# WGPIB.net
KiCad netlist of a schematic drawn in Altium Designer
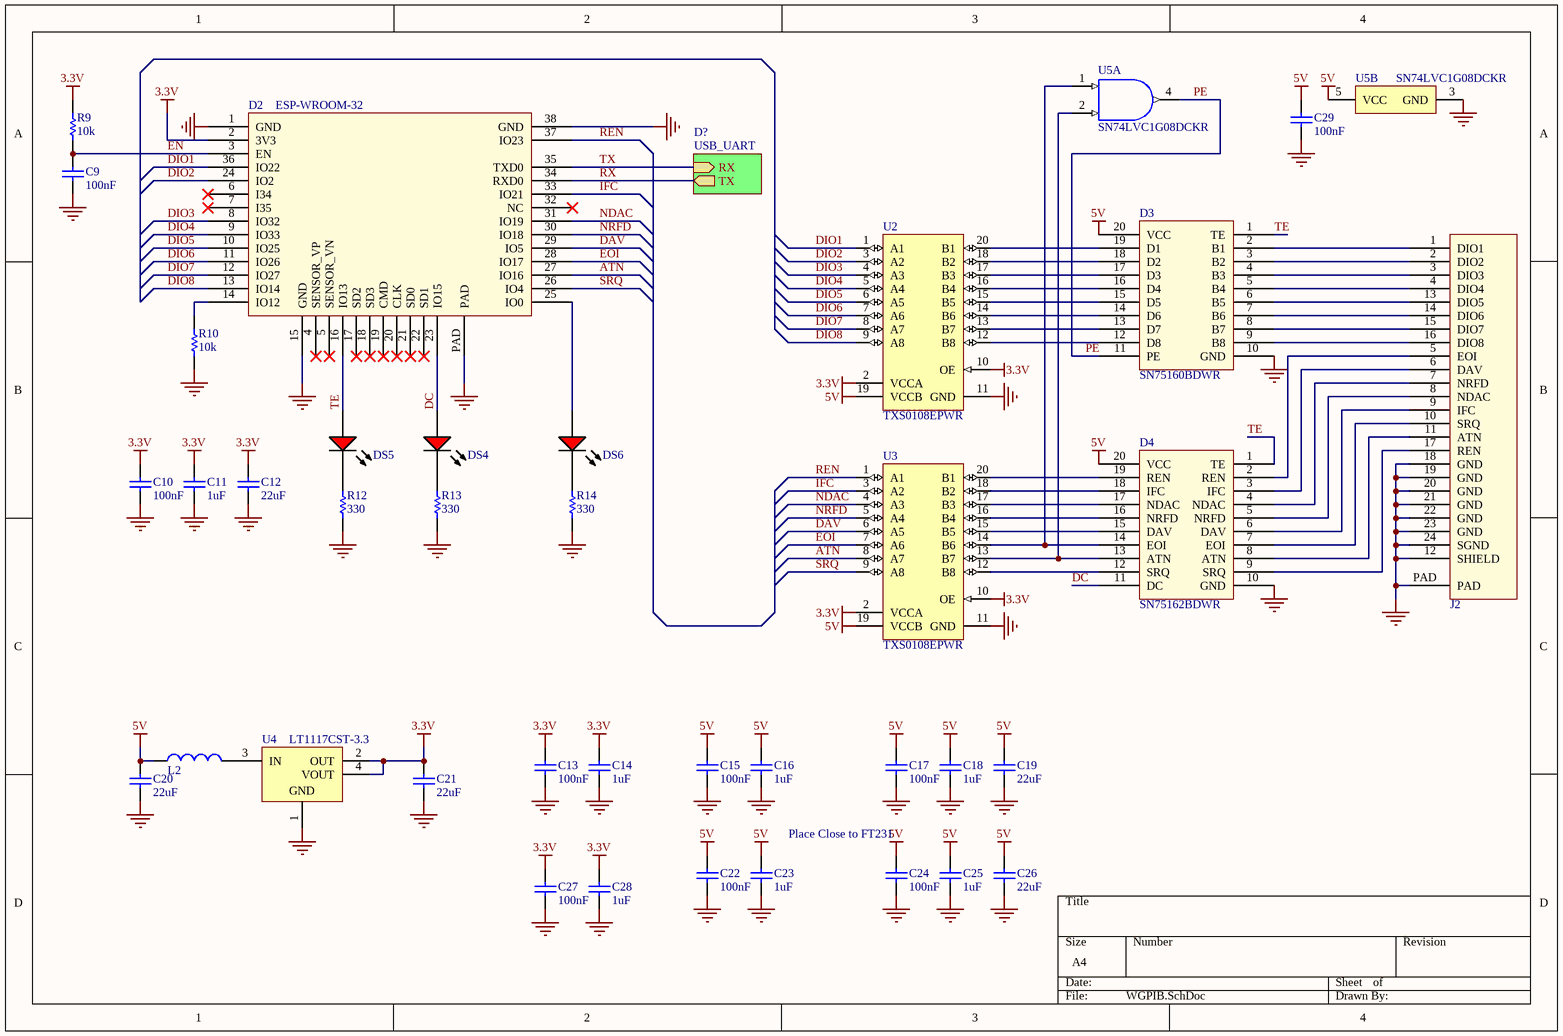
[diagram p0: WGPIB.SchDoc]

(export (version "E")
  (design (tool "Eeschema 10.0.6"))
  (components
    (comp (ref "C9")
      (value "100nF")
      (footprint "CAPC0805(2012)145_N")
      (fields (field (name "TOLERANCE") "Â±20%"))
      (libsource (lib "Altium Content Vault") (part "CAP"))
    )
    (comp (ref "C10")
      (value "100nF")
      (footprint "CAPC0805(2012)145_N")
      (fields (field (name "TOLERANCE") "Â±20%"))
      (libsource (lib "Altium Content Vault") (part "CAP"))
    )
    (comp (ref "C11")
      (value "1uF")
      (footprint "CAPC0805(2012)145_N")
      (fields (field (name "TOLERANCE") "Â±20%"))
      (libsource (lib "Altium Content Vault") (part "CAP"))
    )
    (comp (ref "C12")
      (value "22uF")
      (footprint "CAPC1206(3216)190_M")
      (fields (field (name "TOLERANCE") "Â±20%"))
      (libsource (lib "Altium Content Vault") (part "CAP"))
    )
    (comp (ref "C13")
      (value "100nF")
      (footprint "CAPC0805(2012)145_N")
      (fields (field (name "TOLERANCE") "Â±20%"))
      (libsource (lib "Altium Content Vault") (part "CAP"))
    )
    (comp (ref "C14")
      (value "1uF")
      (footprint "CAPC0805(2012)145_N")
      (fields (field (name "TOLERANCE") "Â±20%"))
      (libsource (lib "Altium Content Vault") (part "CAP"))
    )
    (comp (ref "C15")
      (value "100nF")
      (footprint "CAPC0805(2012)145_N")
      (fields (field (name "TOLERANCE") "Â±20%"))
      (libsource (lib "Altium Content Vault") (part "CAP"))
    )
    (comp (ref "C16")
      (value "1uF")
      (footprint "CAPC0805(2012)145_N")
      (fields (field (name "TOLERANCE") "Â±20%"))
      (libsource (lib "Altium Content Vault") (part "CAP"))
    )
    (comp (ref "C17")
      (value "100nF")
      (footprint "CAPC0805(2012)145_N")
      (fields (field (name "TOLERANCE") "Â±20%"))
      (libsource (lib "Altium Content Vault") (part "CAP"))
    )
    (comp (ref "C18")
      (value "1uF")
      (footprint "CAPC0805(2012)145_N")
      (fields (field (name "TOLERANCE") "Â±20%"))
      (libsource (lib "Altium Content Vault") (part "CAP"))
    )
    (comp (ref "C19")
      (value "22uF")
      (footprint "CAPC1206(3216)190_M")
      (fields (field (name "TOLERANCE") "Â±20%"))
      (libsource (lib "Altium Content Vault") (part "CAP"))
    )
    (comp (ref "C20")
      (value "22uF")
      (footprint "CAPC1206(3216)190_M")
      (fields (field (name "TOLERANCE") "Â±20%"))
      (libsource (lib "Altium Content Vault") (part "CAP"))
    )
    (comp (ref "C21")
      (value "22uF")
      (footprint "CAPC1206(3216)190_M")
      (fields (field (name "TOLERANCE") "Â±20%"))
      (libsource (lib "Altium Content Vault") (part "CAP"))
    )
    (comp (ref "C22")
      (value "100nF")
      (footprint "CAPC0805(2012)145_N")
      (fields (field (name "TOLERANCE") "Â±20%"))
      (libsource (lib "Altium Content Vault") (part "CAP"))
    )
    (comp (ref "C23")
      (value "1uF")
      (footprint "CAPC0805(2012)145_N")
      (fields (field (name "TOLERANCE") "Â±20%"))
      (libsource (lib "Altium Content Vault") (part "CAP"))
    )
    (comp (ref "C24")
      (value "100nF")
      (footprint "CAPC0805(2012)145_N")
      (fields (field (name "TOLERANCE") "Â±20%"))
      (libsource (lib "Altium Content Vault") (part "CAP"))
    )
    (comp (ref "C25")
      (value "1uF")
      (footprint "CAPC0805(2012)145_N")
      (fields (field (name "TOLERANCE") "Â±20%"))
      (libsource (lib "Altium Content Vault") (part "CAP"))
    )
    (comp (ref "C26")
      (value "22uF")
      (footprint "CAPC1206(3216)190_M")
      (fields (field (name "TOLERANCE") "Â±20%"))
      (libsource (lib "Altium Content Vault") (part "CAP"))
    )
    (comp (ref "C27")
      (value "100nF")
      (footprint "CAPC0805(2012)145_N")
      (fields (field (name "TOLERANCE") "Â±20%"))
      (libsource (lib "Altium Content Vault") (part "CAP"))
    )
    (comp (ref "C28")
      (value "1uF")
      (footprint "CAPC0805(2012)145_N")
      (fields (field (name "TOLERANCE") "Â±20%"))
      (libsource (lib "Altium Content Vault") (part "CAP"))
    )
    (comp (ref "C29")
      (value "100nF")
      (footprint "CAPC0805(2012)145_N")
      (fields (field (name "TOLERANCE") "Â±20%"))
      (libsource (lib "Altium Content Vault") (part "CAP"))
    )
    (comp (ref "D2")
      (value "ESP-WROOM-32")
      (footprint "ESP-WROOM-32")
      (description "ESP32 Module")
      (libsource (lib "DEV_Modules") (part "ESP-WROOM-32"))
    )
    (comp (ref "D3")
      (value "SN75160BDWR")
      (footprint "SOIC-20")
      (libsource (lib "LineDrivers") (part "SN75160BDWR"))
    )
    (comp (ref "D4")
      (value "SN75162BDWR")
      (footprint "SOIC-20")
      (libsource (lib "LineDrivers") (part "SN75161BDWR"))
    )
    (comp (ref "DS4")
      (value "TLMS1100-GS08")
      (footprint "VISH-TLMX1100_V")
      (description "LED, RED, 2.1 V, -40 to 100 degC, 2-Pin SMD (0603), RoHS, Tape and Reel")
      (fields (field (name "TOLERANCE") "5%"))
      (libsource (lib "Altium Content Vault") (part "LED-RED-AK-2"))
    )
    (comp (ref "DS5")
      (value "TLMS1100-GS08")
      (footprint "VISH-TLMX1100_V")
      (description "LED, RED, 2.1 V, -40 to 100 degC, 2-Pin SMD (0603), RoHS, Tape and Reel")
      (fields (field (name "TOLERANCE") "5%"))
      (libsource (lib "Altium Content Vault") (part "LED-RED-AK-2"))
    )
    (comp (ref "DS6")
      (value "TLMS1100-GS08")
      (footprint "VISH-TLMX1100_V")
      (description "LED, RED, 2.1 V, -40 to 100 degC, 2-Pin SMD (0603), RoHS, Tape and Reel")
      (fields (field (name "TOLERANCE") "5%"))
      (libsource (lib "Altium Content Vault") (part "LED-RED-AK-2"))
    )
    (comp (ref "J2")
      (value "GPIB")
      (footprint "GPIB THT")
      (description "112-024-113R001")
      (libsource (lib "DSUB_Connector") (part "GPIB"))
    )
    (comp (ref "L2")
      (value "FBMJ2125HM210NT")
      (footprint "INDC2013X105X50LL20T30")
      (description "Chip Inductor, 21 Ohm, +/- 30%, 6 A, -40 to 125 degC, 0805 (2012 Metric), RoHS, Tape and Reel")
      (fields (field (name "TOLERANCE") "30%"))
      (libsource (lib "Altium Content Vault") (part "IND-2"))
    )
    (comp (ref "R9")
      (value "10k")
      (footprint "RESC0805(2012)_M")
      (fields (field (name "POWER") "0.125 W") (field (name "TOLERANCE") "5 %"))
      (libsource (lib "Altium Content Vault") (part "RES"))
    )
    (comp (ref "R10")
      (value "10k")
      (footprint "RESC0805(2012)_M")
      (fields (field (name "POWER") "0.125 W") (field (name "TOLERANCE") "5 %"))
      (libsource (lib "Altium Content Vault") (part "RES"))
    )
    (comp (ref "R12")
      (value "330")
      (footprint "RESC0805(2012)_M")
      (fields (field (name "POWER") "0.125 W") (field (name "TOLERANCE") "5 %"))
      (libsource (lib "Altium Content Vault") (part "RES"))
    )
    (comp (ref "R13")
      (value "330")
      (footprint "RESC0805(2012)_M")
      (fields (field (name "POWER") "0.125 W") (field (name "TOLERANCE") "5 %"))
      (libsource (lib "Altium Content Vault") (part "RES"))
    )
    (comp (ref "R14")
      (value "330")
      (footprint "RESC0805(2012)_M")
      (fields (field (name "POWER") "0.125 W") (field (name "TOLERANCE") "5 %"))
      (libsource (lib "Altium Content Vault") (part "RES"))
    )
    (comp (ref "U2")
      (value "TXS0108EPWR")
      (footprint "PW0020A_M")
      (fields (field (name "MANUFACTURER") "Texas Instruments"))
      (libsource (lib "Altium Content Vault") (part "TI-TXS0108EPWR-SOP-20"))
    )
    (comp (ref "U3")
      (value "TXS0108EPWR")
      (footprint "PW0020A_M")
      (fields (field (name "MANUFACTURER") "Texas Instruments"))
      (libsource (lib "Altium Content Vault") (part "TI-TXS0108EPWR-SOP-20"))
    )
    (comp (ref "U4")
      (value "LT1117CST-3.3")
      (footprint "LT-ST-3-SOT-223_M")
      (fields (field (name "MANUFACTURER") "Linear Technology"))
      (libsource (lib "Altium Content Vault") (part "LT-LT1117-3_B"))
    )
    (comp (ref "U5")
      (value "SN74LVC1G08DCKR")
      (footprint "DCK0005A_M")
      (description "Single 2-Input Positive-AND Gate, DCK0005A, LARGE T&R")
      (fields
        (field (name "GENERIC PART NUMBER") "SN74LVC1G08")
        (field (name "MANUFACTURER") "Texas Instruments")
      )
      (libsource (lib "Altium Content Vault") (part "TI-SN74XXX1X08-5"))
    )
  )
  (nets
    (net (code "1") (name "/ATN") (class "Default")
      (node (ref "D2") (pin "27") (pinfunction "IO16_27") (pintype "passive"))
      (node (ref "U3") (pin "8") (pinfunction "A7_8") (pintype "bidirectional"))
    )
    (net (code "2") (name "/DAV") (class "Default")
      (node (ref "D2") (pin "29") (pinfunction "IO5_29") (pintype "passive"))
      (node (ref "U3") (pin "6") (pinfunction "A5_6") (pintype "bidirectional"))
    )
    (net (code "3") (name "/DC") (class "Default")
      (node (ref "D2") (pin "23") (pinfunction "IO15_23") (pintype "passive"))
      (node (ref "D4") (pin "11") (pinfunction "DC_11") (pintype "passive"))
      (node (ref "DS4") (pin "1") (pinfunction "A_1") (pintype "passive"))
    )
    (net (code "4") (name "/DIO1") (class "Default")
      (node (ref "D2") (pin "36") (pinfunction "IO22_36") (pintype "passive"))
      (node (ref "U2") (pin "1") (pinfunction "A1_1") (pintype "bidirectional"))
    )
    (net (code "5") (name "/DIO2") (class "Default")
      (node (ref "D2") (pin "24") (pinfunction "IO2_24") (pintype "passive"))
      (node (ref "U2") (pin "3") (pinfunction "A2_3") (pintype "bidirectional"))
    )
    (net (code "6") (name "/DIO3") (class "Default")
      (node (ref "D2") (pin "8") (pinfunction "IO32_8") (pintype "passive"))
      (node (ref "U2") (pin "4") (pinfunction "A3_4") (pintype "bidirectional"))
    )
    (net (code "7") (name "/DIO4") (class "Default")
      (node (ref "D2") (pin "9") (pinfunction "IO33_9") (pintype "passive"))
      (node (ref "U2") (pin "5") (pinfunction "A4_5") (pintype "bidirectional"))
    )
    (net (code "8") (name "/DIO5") (class "Default")
      (node (ref "D2") (pin "10") (pinfunction "IO25_10") (pintype "passive"))
      (node (ref "U2") (pin "6") (pinfunction "A5_6") (pintype "bidirectional"))
    )
    (net (code "9") (name "/DIO6") (class "Default")
      (node (ref "D2") (pin "11") (pinfunction "IO26_11") (pintype "passive"))
      (node (ref "U2") (pin "7") (pinfunction "A6_7") (pintype "bidirectional"))
    )
    (net (code "10") (name "/DIO7") (class "Default")
      (node (ref "D2") (pin "12") (pinfunction "IO27_12") (pintype "passive"))
      (node (ref "U2") (pin "8") (pinfunction "A7_8") (pintype "bidirectional"))
    )
    (net (code "11") (name "/DIO8") (class "Default")
      (node (ref "D2") (pin "13") (pinfunction "IO14_13") (pintype "passive"))
      (node (ref "U2") (pin "9") (pinfunction "A8_9") (pintype "bidirectional"))
    )
    (net (code "12") (name "/EN") (class "Default")
      (node (ref "C9") (pin "2") (pinfunction "2_2") (pintype "passive"))
      (node (ref "D2") (pin "3") (pinfunction "EN_3") (pintype "passive"))
      (node (ref "R9") (pin "1") (pinfunction "1_1") (pintype "passive"))
    )
    (net (code "13") (name "/EOI") (class "Default")
      (node (ref "D2") (pin "28") (pinfunction "IO17_28") (pintype "passive"))
      (node (ref "U3") (pin "7") (pinfunction "A6_7") (pintype "bidirectional"))
    )
    (net (code "14") (name "/IFC") (class "Default")
      (node (ref "D2") (pin "33") (pinfunction "IO21_33") (pintype "passive"))
      (node (ref "U3") (pin "3") (pinfunction "A2_3") (pintype "bidirectional"))
    )
    (net (code "15") (name "/NDAC") (class "Default")
      (node (ref "D2") (pin "31") (pinfunction "IO19_31") (pintype "passive"))
      (node (ref "U3") (pin "4") (pinfunction "A3_4") (pintype "bidirectional"))
    )
    (net (code "16") (name "/NRFD") (class "Default")
      (node (ref "D2") (pin "30") (pinfunction "IO18_30") (pintype "passive"))
      (node (ref "U3") (pin "5") (pinfunction "A4_5") (pintype "bidirectional"))
    )
    (net (code "17") (name "/PE") (class "Default")
      (node (ref "D3") (pin "11") (pinfunction "PE_11") (pintype "passive"))
      (node (ref "U5") (pin "4") (pinfunction "Y_4") (pintype "output"))
    )
    (net (code "18") (name "/REN") (class "Default")
      (node (ref "D2") (pin "37") (pinfunction "IO23_37") (pintype "passive"))
      (node (ref "U3") (pin "1") (pinfunction "A1_1") (pintype "bidirectional"))
    )
    (net (code "19") (name "/RX") (class "Default")
      (node (ref "D2") (pin "34") (pinfunction "RXD0_34") (pintype "passive"))
    )
    (net (code "20") (name "/SRQ") (class "Default")
      (node (ref "D2") (pin "26") (pinfunction "IO4_26") (pintype "passive"))
      (node (ref "U3") (pin "9") (pinfunction "A8_9") (pintype "bidirectional"))
    )
    (net (code "21") (name "/TE") (class "Default")
      (node (ref "D2") (pin "16") (pinfunction "IO13_16") (pintype "passive"))
      (node (ref "D3") (pin "1") (pinfunction "TE_1") (pintype "passive"))
      (node (ref "D4") (pin "1") (pinfunction "TE_1") (pintype "passive"))
      (node (ref "DS5") (pin "1") (pinfunction "A_1") (pintype "passive"))
    )
    (net (code "22") (name "/TX") (class "Default")
      (node (ref "D2") (pin "35") (pinfunction "TXD0_35") (pintype "passive"))
    )
    (net (code "23") (name "3.3V") (class "Default")
      (node (ref "C10") (pin "2") (pinfunction "2_2") (pintype "passive"))
      (node (ref "C11") (pin "2") (pinfunction "2_2") (pintype "passive"))
      (node (ref "C12") (pin "2") (pinfunction "2_2") (pintype "passive"))
      (node (ref "C13") (pin "2") (pinfunction "2_2") (pintype "passive"))
      (node (ref "C14") (pin "2") (pinfunction "2_2") (pintype "passive"))
      (node (ref "C21") (pin "2") (pinfunction "2_2") (pintype "passive"))
      (node (ref "C27") (pin "2") (pinfunction "2_2") (pintype "passive"))
      (node (ref "C28") (pin "2") (pinfunction "2_2") (pintype "passive"))
      (node (ref "D2") (pin "2") (pinfunction "3V3_2") (pintype "passive"))
      (node (ref "R9") (pin "2") (pinfunction "2_2") (pintype "passive"))
      (node (ref "U2") (pin "10") (pinfunction "OE_10") (pintype "input"))
      (node (ref "U2") (pin "2") (pinfunction "VCCA_2") (pintype "power_in"))
      (node (ref "U3") (pin "10") (pinfunction "OE_10") (pintype "input"))
      (node (ref "U3") (pin "2") (pinfunction "VCCA_2") (pintype "power_in"))
      (node (ref "U4") (pin "2") (pinfunction "OUT_2") (pintype "power_in"))
      (node (ref "U4") (pin "4") (pinfunction "VOUT_4") (pintype "power_in"))
    )
    (net (code "24") (name "5V") (class "Default")
      (node (ref "C15") (pin "2") (pinfunction "2_2") (pintype "passive"))
      (node (ref "C16") (pin "2") (pinfunction "2_2") (pintype "passive"))
      (node (ref "C17") (pin "2") (pinfunction "2_2") (pintype "passive"))
      (node (ref "C18") (pin "2") (pinfunction "2_2") (pintype "passive"))
      (node (ref "C19") (pin "2") (pinfunction "2_2") (pintype "passive"))
      (node (ref "C20") (pin "2") (pinfunction "2_2") (pintype "passive"))
      (node (ref "C22") (pin "2") (pinfunction "2_2") (pintype "passive"))
      (node (ref "C23") (pin "2") (pinfunction "2_2") (pintype "passive"))
      (node (ref "C24") (pin "2") (pinfunction "2_2") (pintype "passive"))
      (node (ref "C25") (pin "2") (pinfunction "2_2") (pintype "passive"))
      (node (ref "C26") (pin "2") (pinfunction "2_2") (pintype "passive"))
      (node (ref "C29") (pin "2") (pinfunction "2_2") (pintype "passive"))
      (node (ref "D3") (pin "20") (pinfunction "VCC_20") (pintype "passive"))
      (node (ref "D4") (pin "20") (pinfunction "VCC_20") (pintype "passive"))
      (node (ref "L2") (pin "1") (pinfunction "1_1") (pintype "passive"))
      (node (ref "U2") (pin "19") (pinfunction "VCCB_19") (pintype "power_in"))
      (node (ref "U3") (pin "19") (pinfunction "VCCB_19") (pintype "power_in"))
      (node (ref "U5") (pin "5") (pinfunction "VCC_5") (pintype "power_in"))
    )
    (net (code "25") (name "GND") (class "Default")
      (node (ref "C10") (pin "1") (pinfunction "1_1") (pintype "passive"))
      (node (ref "C11") (pin "1") (pinfunction "1_1") (pintype "passive"))
      (node (ref "C12") (pin "1") (pinfunction "1_1") (pintype "passive"))
      (node (ref "C13") (pin "1") (pinfunction "1_1") (pintype "passive"))
      (node (ref "C14") (pin "1") (pinfunction "1_1") (pintype "passive"))
      (node (ref "C15") (pin "1") (pinfunction "1_1") (pintype "passive"))
      (node (ref "C16") (pin "1") (pinfunction "1_1") (pintype "passive"))
      (node (ref "C17") (pin "1") (pinfunction "1_1") (pintype "passive"))
      (node (ref "C18") (pin "1") (pinfunction "1_1") (pintype "passive"))
      (node (ref "C19") (pin "1") (pinfunction "1_1") (pintype "passive"))
      (node (ref "C20") (pin "1") (pinfunction "1_1") (pintype "passive"))
      (node (ref "C21") (pin "1") (pinfunction "1_1") (pintype "passive"))
      (node (ref "C22") (pin "1") (pinfunction "1_1") (pintype "passive"))
      (node (ref "C23") (pin "1") (pinfunction "1_1") (pintype "passive"))
      (node (ref "C24") (pin "1") (pinfunction "1_1") (pintype "passive"))
      (node (ref "C25") (pin "1") (pinfunction "1_1") (pintype "passive"))
      (node (ref "C26") (pin "1") (pinfunction "1_1") (pintype "passive"))
      (node (ref "C27") (pin "1") (pinfunction "1_1") (pintype "passive"))
      (node (ref "C28") (pin "1") (pinfunction "1_1") (pintype "passive"))
      (node (ref "C29") (pin "1") (pinfunction "1_1") (pintype "passive"))
      (node (ref "C9") (pin "1") (pinfunction "1_1") (pintype "passive"))
      (node (ref "D2") (pin "1") (pinfunction "GND_1") (pintype "passive"))
      (node (ref "D2") (pin "15") (pinfunction "GND_15") (pintype "passive"))
      (node (ref "D2") (pin "38") (pinfunction "GND_38") (pintype "passive"))
      (node (ref "D2") (pin "PAD") (pinfunction "PAD_PAD") (pintype "passive"))
      (node (ref "D3") (pin "10") (pinfunction "GND_10") (pintype "passive"))
      (node (ref "D4") (pin "10") (pinfunction "GND_10") (pintype "passive"))
      (node (ref "J2") (pin "12") (pinfunction "SHIELD_12") (pintype "passive"))
      (node (ref "J2") (pin "18") (pinfunction "GND_18") (pintype "passive"))
      (node (ref "J2") (pin "19") (pinfunction "GND_19") (pintype "passive"))
      (node (ref "J2") (pin "20") (pinfunction "GND_20") (pintype "passive"))
      (node (ref "J2") (pin "21") (pinfunction "GND_21") (pintype "passive"))
      (node (ref "J2") (pin "22") (pinfunction "GND_22") (pintype "passive"))
      (node (ref "J2") (pin "23") (pinfunction "GND_23") (pintype "passive"))
      (node (ref "J2") (pin "24") (pinfunction "SGND_24") (pintype "passive"))
      (node (ref "J2") (pin "PAD") (pinfunction "PAD_PAD") (pintype "passive"))
      (node (ref "R10") (pin "1") (pinfunction "1_1") (pintype "passive"))
      (node (ref "R12") (pin "1") (pinfunction "1_1") (pintype "passive"))
      (node (ref "R13") (pin "1") (pinfunction "1_1") (pintype "passive"))
      (node (ref "R14") (pin "1") (pinfunction "1_1") (pintype "passive"))
      (node (ref "U2") (pin "11") (pinfunction "GND_11") (pintype "power_in"))
      (node (ref "U3") (pin "11") (pinfunction "GND_11") (pintype "power_in"))
      (node (ref "U4") (pin "1") (pinfunction "GND_1") (pintype "power_in"))
      (node (ref "U5") (pin "3") (pinfunction "GND_3") (pintype "power_in"))
    )
    (net (code "26") (name "Net-(D2-IO0)") (class "Default")
      (node (ref "D2") (pin "25") (pinfunction "IO0_25") (pintype "passive"))
      (node (ref "DS6") (pin "1") (pinfunction "A_1") (pintype "passive"))
    )
    (net (code "27") (name "Net-(D2-IO12)") (class "Default")
      (node (ref "D2") (pin "14") (pinfunction "IO12_14") (pintype "passive"))
      (node (ref "R10") (pin "2") (pinfunction "2_2") (pintype "passive"))
    )
    (net (code "28") (name "Net-(D3-B1)") (class "Default")
      (node (ref "D3") (pin "2") (pinfunction "B1_2") (pintype "passive"))
      (node (ref "J2") (pin "1") (pinfunction "DIO1_1") (pintype "passive"))
    )
    (net (code "29") (name "Net-(D3-B2)") (class "Default")
      (node (ref "D3") (pin "3") (pinfunction "B2_3") (pintype "passive"))
      (node (ref "J2") (pin "2") (pinfunction "DIO2_2") (pintype "passive"))
    )
    (net (code "30") (name "Net-(D3-B3)") (class "Default")
      (node (ref "D3") (pin "4") (pinfunction "B3_4") (pintype "passive"))
      (node (ref "J2") (pin "3") (pinfunction "DIO3_3") (pintype "passive"))
    )
    (net (code "31") (name "Net-(D3-B4)") (class "Default")
      (node (ref "D3") (pin "5") (pinfunction "B4_5") (pintype "passive"))
      (node (ref "J2") (pin "4") (pinfunction "DIO4_4") (pintype "passive"))
    )
    (net (code "32") (name "Net-(D3-B5)") (class "Default")
      (node (ref "D3") (pin "6") (pinfunction "B5_6") (pintype "passive"))
      (node (ref "J2") (pin "13") (pinfunction "DIO5_13") (pintype "passive"))
    )
    (net (code "33") (name "Net-(D3-B6)") (class "Default")
      (node (ref "D3") (pin "7") (pinfunction "B6_7") (pintype "passive"))
      (node (ref "J2") (pin "14") (pinfunction "DIO6_14") (pintype "passive"))
    )
    (net (code "34") (name "Net-(D3-B7)") (class "Default")
      (node (ref "D3") (pin "8") (pinfunction "B7_8") (pintype "passive"))
      (node (ref "J2") (pin "15") (pinfunction "DIO7_15") (pintype "passive"))
    )
    (net (code "35") (name "Net-(D3-B8)") (class "Default")
      (node (ref "D3") (pin "9") (pinfunction "B8_9") (pintype "passive"))
      (node (ref "J2") (pin "16") (pinfunction "DIO8_16") (pintype "passive"))
    )
    (net (code "36") (name "Net-(D3-D1)") (class "Default")
      (node (ref "D3") (pin "19") (pinfunction "D1_19") (pintype "passive"))
      (node (ref "U2") (pin "20") (pinfunction "B1_20") (pintype "bidirectional"))
    )
    (net (code "37") (name "Net-(D3-D2)") (class "Default")
      (node (ref "D3") (pin "18") (pinfunction "D2_18") (pintype "passive"))
      (node (ref "U2") (pin "18") (pinfunction "B2_18") (pintype "bidirectional"))
    )
    (net (code "38") (name "Net-(D3-D3)") (class "Default")
      (node (ref "D3") (pin "17") (pinfunction "D3_17") (pintype "passive"))
      (node (ref "U2") (pin "17") (pinfunction "B3_17") (pintype "bidirectional"))
    )
    (net (code "39") (name "Net-(D3-D4)") (class "Default")
      (node (ref "D3") (pin "16") (pinfunction "D4_16") (pintype "passive"))
      (node (ref "U2") (pin "16") (pinfunction "B4_16") (pintype "bidirectional"))
    )
    (net (code "40") (name "Net-(D3-D5)") (class "Default")
      (node (ref "D3") (pin "15") (pinfunction "D5_15") (pintype "passive"))
      (node (ref "U2") (pin "15") (pinfunction "B5_15") (pintype "bidirectional"))
    )
    (net (code "41") (name "Net-(D3-D6)") (class "Default")
      (node (ref "D3") (pin "14") (pinfunction "D6_14") (pintype "passive"))
      (node (ref "U2") (pin "14") (pinfunction "B6_14") (pintype "bidirectional"))
    )
    (net (code "42") (name "Net-(D3-D7)") (class "Default")
      (node (ref "D3") (pin "13") (pinfunction "D7_13") (pintype "passive"))
      (node (ref "U2") (pin "13") (pinfunction "B7_13") (pintype "bidirectional"))
    )
    (net (code "43") (name "Net-(D3-D8)") (class "Default")
      (node (ref "D3") (pin "12") (pinfunction "D8_12") (pintype "passive"))
      (node (ref "U2") (pin "12") (pinfunction "B8_12") (pintype "bidirectional"))
    )
    (net (code "44") (name "Net-(DS4-K)") (class "Default")
      (node (ref "DS4") (pin "2") (pinfunction "K_2") (pintype "passive"))
      (node (ref "R13") (pin "2") (pinfunction "2_2") (pintype "passive"))
    )
    (net (code "45") (name "Net-(DS5-K)") (class "Default")
      (node (ref "DS5") (pin "2") (pinfunction "K_2") (pintype "passive"))
      (node (ref "R12") (pin "2") (pinfunction "2_2") (pintype "passive"))
    )
    (net (code "46") (name "Net-(DS6-K)") (class "Default")
      (node (ref "DS6") (pin "2") (pinfunction "K_2") (pintype "passive"))
      (node (ref "R14") (pin "2") (pinfunction "2_2") (pintype "passive"))
    )
    (net (code "47") (name "Net-(J2-ATN)") (class "Default")
      (node (ref "D4") (pin "8") (pinfunction "ATN_8") (pintype "passive"))
      (node (ref "J2") (pin "11") (pinfunction "ATN_11") (pintype "passive"))
    )
    (net (code "48") (name "Net-(J2-DAV)") (class "Default")
      (node (ref "D4") (pin "3") (pinfunction "IFC_3") (pintype "passive"))
      (node (ref "J2") (pin "6") (pinfunction "DAV_6") (pintype "passive"))
    )
    (net (code "49") (name "Net-(J2-EOI)") (class "Default")
      (node (ref "D4") (pin "2") (pinfunction "REN_2") (pintype "passive"))
      (node (ref "J2") (pin "5") (pinfunction "EOI_5") (pintype "passive"))
    )
    (net (code "50") (name "Net-(J2-IFC)") (class "Default")
      (node (ref "D4") (pin "6") (pinfunction "DAV_6") (pintype "passive"))
      (node (ref "J2") (pin "9") (pinfunction "IFC_9") (pintype "passive"))
    )
    (net (code "51") (name "Net-(J2-NDAC)") (class "Default")
      (node (ref "D4") (pin "5") (pinfunction "NRFD_5") (pintype "passive"))
      (node (ref "J2") (pin "8") (pinfunction "NDAC_8") (pintype "passive"))
    )
    (net (code "52") (name "Net-(J2-NRFD)") (class "Default")
      (node (ref "D4") (pin "4") (pinfunction "NDAC_4") (pintype "passive"))
      (node (ref "J2") (pin "7") (pinfunction "NRFD_7") (pintype "passive"))
    )
    (net (code "53") (name "Net-(J2-REN)") (class "Default")
      (node (ref "D4") (pin "9") (pinfunction "SRQ_9") (pintype "passive"))
      (node (ref "J2") (pin "17") (pinfunction "REN_17") (pintype "passive"))
    )
    (net (code "54") (name "Net-(J2-SRQ)") (class "Default")
      (node (ref "D4") (pin "7") (pinfunction "EOI_7") (pintype "passive"))
      (node (ref "J2") (pin "10") (pinfunction "SRQ_10") (pintype "passive"))
    )
    (net (code "55") (name "Net-(U3-B1)") (class "Default")
      (node (ref "D4") (pin "19") (pinfunction "REN_19") (pintype "passive"))
      (node (ref "U3") (pin "20") (pinfunction "B1_20") (pintype "bidirectional"))
    )
    (net (code "56") (name "Net-(U3-B2)") (class "Default")
      (node (ref "D4") (pin "18") (pinfunction "IFC_18") (pintype "passive"))
      (node (ref "U3") (pin "18") (pinfunction "B2_18") (pintype "bidirectional"))
    )
    (net (code "57") (name "Net-(U3-B3)") (class "Default")
      (node (ref "D4") (pin "17") (pinfunction "NDAC_17") (pintype "passive"))
      (node (ref "U3") (pin "17") (pinfunction "B3_17") (pintype "bidirectional"))
    )
    (net (code "58") (name "Net-(U3-B4)") (class "Default")
      (node (ref "D4") (pin "16") (pinfunction "NRFD_16") (pintype "passive"))
      (node (ref "U3") (pin "16") (pinfunction "B4_16") (pintype "bidirectional"))
    )
    (net (code "59") (name "Net-(U3-B5)") (class "Default")
      (node (ref "D4") (pin "15") (pinfunction "DAV_15") (pintype "passive"))
      (node (ref "U3") (pin "15") (pinfunction "B5_15") (pintype "bidirectional"))
    )
    (net (code "60") (name "Net-(U3-B6)") (class "Default")
      (node (ref "D4") (pin "14") (pinfunction "EOI_14") (pintype "passive"))
      (node (ref "U3") (pin "14") (pinfunction "B6_14") (pintype "bidirectional"))
      (node (ref "U5") (pin "1") (pinfunction "A_1") (pintype "input"))
    )
    (net (code "61") (name "Net-(U3-B7)") (class "Default")
      (node (ref "D4") (pin "13") (pinfunction "ATN_13") (pintype "passive"))
      (node (ref "U3") (pin "13") (pinfunction "B7_13") (pintype "bidirectional"))
      (node (ref "U5") (pin "2") (pinfunction "B_2") (pintype "input"))
    )
    (net (code "62") (name "Net-(U3-B8)") (class "Default")
      (node (ref "D4") (pin "12") (pinfunction "SRQ_12") (pintype "passive"))
      (node (ref "U3") (pin "12") (pinfunction "B8_12") (pintype "bidirectional"))
    )
    (net (code "63") (name "Net-(U4-IN)") (class "Default")
      (node (ref "L2") (pin "2") (pinfunction "2_2") (pintype "passive"))
      (node (ref "U4") (pin "3") (pinfunction "IN_3") (pintype "power_in"))
    )
    (net (code "64") (name "unconnected-(D2-CLK-Pad20)") (class "Default")
      (node (ref "D2") (pin "20") (pinfunction "CLK_20") (pintype "passive+no_connect"))
    )
    (net (code "65") (name "unconnected-(D2-CMD-Pad19)") (class "Default")
      (node (ref "D2") (pin "19") (pinfunction "CMD_19") (pintype "passive+no_connect"))
    )
    (net (code "66") (name "unconnected-(D2-I34-Pad6)") (class "Default")
      (node (ref "D2") (pin "6") (pinfunction "I34_6") (pintype "passive+no_connect"))
    )
    (net (code "67") (name "unconnected-(D2-I35-Pad7)") (class "Default")
      (node (ref "D2") (pin "7") (pinfunction "I35_7") (pintype "passive+no_connect"))
    )
    (net (code "68") (name "unconnected-(D2-NC-Pad32)") (class "Default")
      (node (ref "D2") (pin "32") (pinfunction "NC_32") (pintype "passive+no_connect"))
    )
    (net (code "69") (name "unconnected-(D2-SD0-Pad21)") (class "Default")
      (node (ref "D2") (pin "21") (pinfunction "SD0_21") (pintype "passive+no_connect"))
    )
    (net (code "70") (name "unconnected-(D2-SD1-Pad22)") (class "Default")
      (node (ref "D2") (pin "22") (pinfunction "SD1_22") (pintype "passive+no_connect"))
    )
    (net (code "71") (name "unconnected-(D2-SD2-Pad17)") (class "Default")
      (node (ref "D2") (pin "17") (pinfunction "SD2_17") (pintype "passive+no_connect"))
    )
    (net (code "72") (name "unconnected-(D2-SD3-Pad18)") (class "Default")
      (node (ref "D2") (pin "18") (pinfunction "SD3_18") (pintype "passive+no_connect"))
    )
    (net (code "73") (name "unconnected-(D2-SENSOR_VN-Pad5)") (class "Default")
      (node (ref "D2") (pin "5") (pinfunction "SENSOR_VN_5") (pintype "passive+no_connect"))
    )
    (net (code "74") (name "unconnected-(D2-SENSOR_VP-Pad4)") (class "Default")
      (node (ref "D2") (pin "4") (pinfunction "SENSOR_VP_4") (pintype "passive+no_connect"))
    )
  )
)
